# SD_USB_FMU3_REV_G.net
KiCad netlist of a schematic drawn in Altium Designer
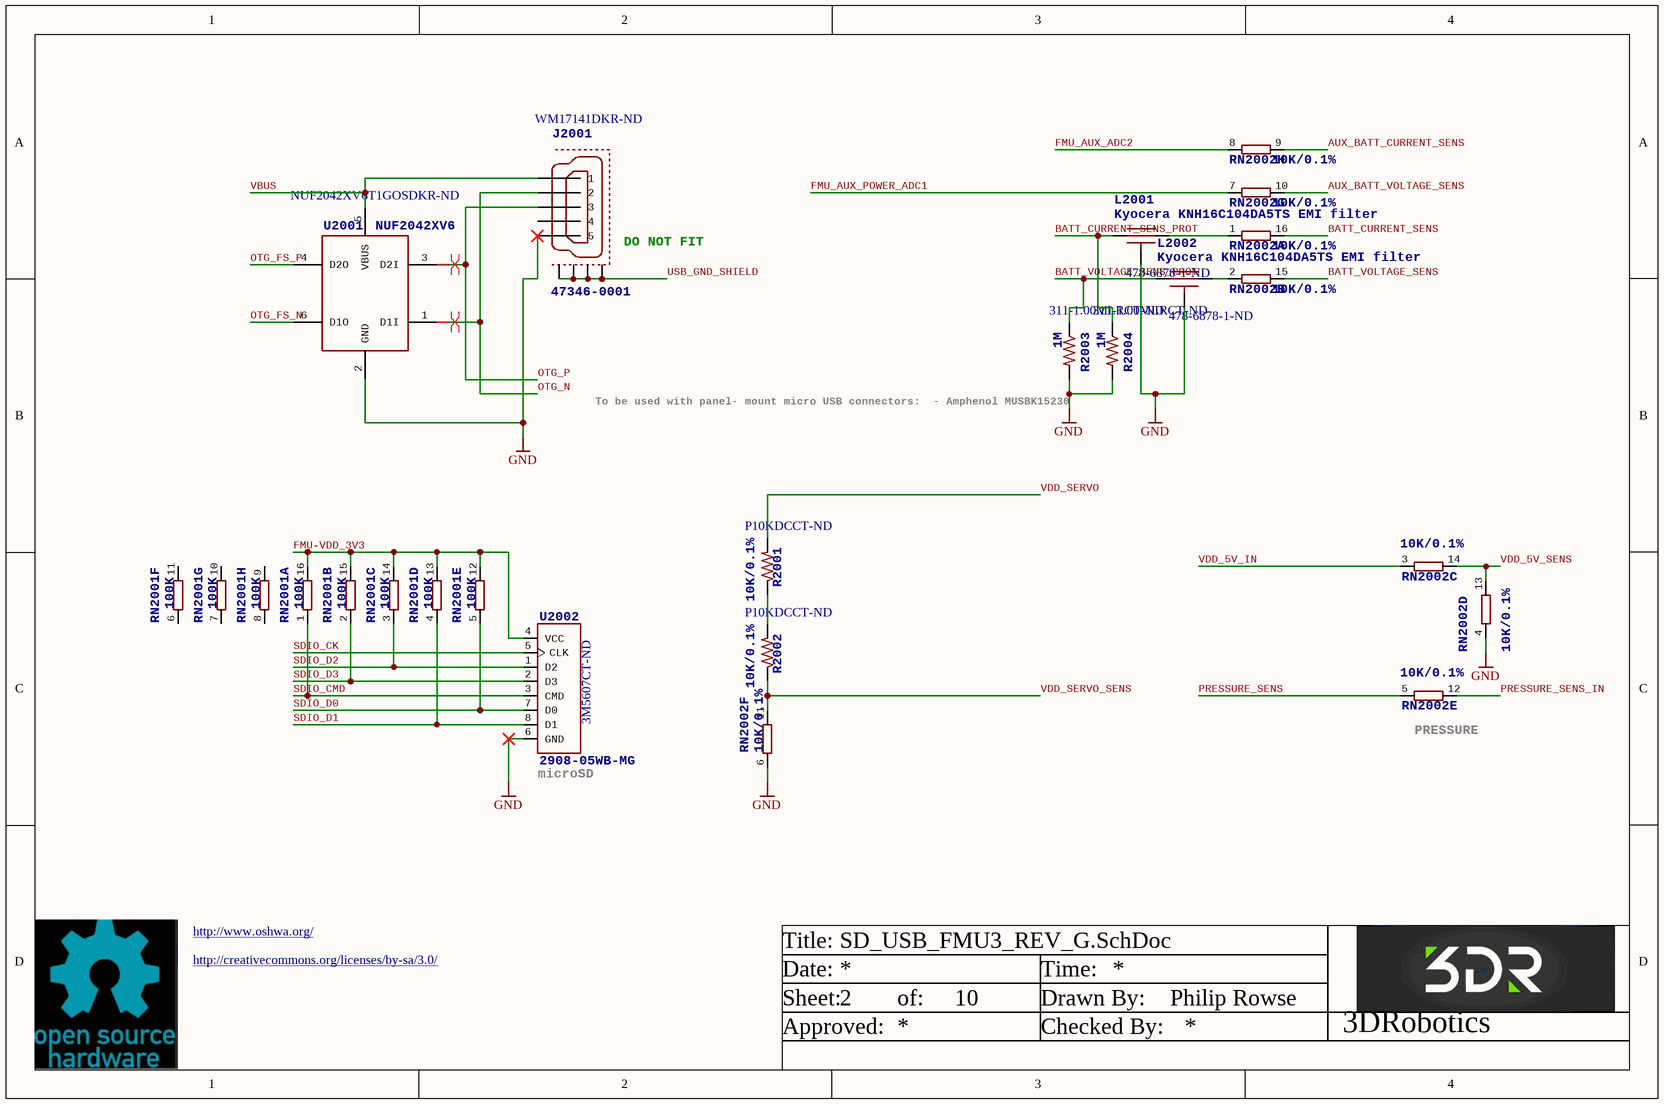
[diagram p0: SD_USB_FMU3_REV_G.SchDoc]

(export (version "E")
  (design (tool "Eeschema 10.0.6"))
  (components
    (comp (ref "J2001")
      (value "47346-0001")
      (footprint "MOLEX-47346-0001")
      (description "MICRO USB B, BOTTOM MOUNT")
      (fields
        (field (name "SUPPLIER PART NUMBER 1") "WM17141DKR-ND")
        (field (name "3DR_PARTNO") "ECM0486")
        (field (name "PARTNO") "0473460001")
      )
      (libsource (lib "pixhawk2") (part "MOLEX-47346-0001"))
    )
    (comp (ref "L2001")
      (value "Kyocera KNH16C104DA5TS EMI filter")
      (footprint "KYOCERA-KNH16-DA")
      (description "FILTER CAP 0.1UF 2A 25V 0603")
      (fields
        (field (name "SUPPLIER PART NUMBER 1") "478-6878-1-ND")
        (field (name "3DR_PARTNO") "ECM0719")
        (field (name "PARTNO") "KNH16C104DA5TS")
      )
      (libsource (lib "pixhawk2") (part "KNH16C104DA5TS"))
    )
    (comp (ref "L2002")
      (value "Kyocera KNH16C104DA5TS EMI filter")
      (footprint "KYOCERA-KNH16-DA")
      (description "FILTER CAP 0.1UF 2A 25V 0603")
      (fields
        (field (name "SUPPLIER PART NUMBER 1") "478-6878-1-ND")
        (field (name "3DR_PARTNO") "ECM0719")
        (field (name "PARTNO") "KNH16C104DA5TS")
      )
      (libsource (lib "pixhawk2") (part "KNH16C104DA5TS"))
    )
    (comp (ref "R2001")
      (value "10K/0.1%")
      (footprint "0402-RES")
      (description "RES 10K OHM 1/16W .1% 0402 SMD")
      (fields
        (field (name "SUPPLIER PART NUMBER 1") "P10KDCCT-ND")
        (field (name "3DR_PARTNO") "ECM0810")
        (field (name "PARTNO") "ERA-2AEB103X")
      )
      (libsource (lib "pixhawk2") (part "RESISTOR0402-RES"))
    )
    (comp (ref "R2002")
      (value "10K/0.1%")
      (footprint "0402-RES")
      (description "RES 10K OHM 1/16W .1% 0402 SMD")
      (fields
        (field (name "SUPPLIER PART NUMBER 1") "P10KDCCT-ND")
        (field (name "3DR_PARTNO") "ECM0810")
        (field (name "PARTNO") "ERA-2AEB103X")
      )
      (libsource (lib "pixhawk2") (part "RESISTOR0402-RES"))
    )
    (comp (ref "R2003")
      (value "1M")
      (footprint "0402-RES")
      (description "RES 1M OHM 1/16W 1% 0402 SMD")
      (fields
        (field (name "PARTNO") "RC0402FR-071ML")
        (field (name "SUPPLIER PART NUMBER 1") "311-1.00MLRCT-ND")
        (field (name "3DR_PARTNO") "ECM0806")
      )
      (libsource (lib "pixhawk2") (part "RESISTOR0402-RES"))
    )
    (comp (ref "R2004")
      (value "1M")
      (footprint "0402-RES")
      (description "RES 1M OHM 1/16W 1% 0402 SMD")
      (fields
        (field (name "PARTNO") "RC0402FR-071ML")
        (field (name "SUPPLIER PART NUMBER 1") "311-1.00MLRCT-ND")
        (field (name "3DR_PARTNO") "ECM0806")
      )
      (libsource (lib "pixhawk2") (part "RESISTOR0402-RES"))
    )
    (comp (ref "RN2001")
      (value "100K")
      (footprint "EXB2HV")
      (description "RES ARRAY 100K OHM 8 RES 1506")
      (fields (field (name "PARTNO") "EXB-2HV104JV") (field (name "3DR_PARTNO") "ECM0101"))
      (libsource (lib "pixhawk2") (part "8R-NEXB2HV-100K"))
    )
    (comp (ref "RN2002")
      (value "10K/0.1%")
      (footprint "EXB2HV")
      (description "RES ARRAY 10K OHM 8 RES 1506")
      (fields (field (name "PARTNO") "EXB-2HV103JV") (field (name "3DR_PARTNO") "ECM0546"))
      (libsource (lib "pixhawk2") (part "8R-NEXB2HV-10K"))
    )
    (comp (ref "U2001")
      (value "NUF2042XV6")
      (footprint "SOT563-6")
      (description "IC FILTER USB ESD PROTECT SOT363")
      (fields
        (field (name "PARTNO") "NUF2042XV6T1G")
        (field (name "SUPPLIER PART NUMBER 1") "NUF2042XV6T1GOSDKR-ND")
        (field (name "3DR_PARTNO") "ECM0836")
      )
      (libsource (lib "pixhawk2") (part "NUF2042XV6"))
    )
    (comp (ref "U2002")
      (value "2908-05WB-MG")
      (footprint "MICROSD")
      (description "CONN MICRO SD CARD PUSH-PUSH R/A")
      (fields (field (name "SUPPLIER PART NUMBER 1") "3M5607CT-ND") (field (name "3DR_PARTNO") "ECM0485"))
      (libsource (lib "baseboard") (part "MICROSDSDI"))
    )
  )
  (nets
    (net (code "1") (name "/AUX_BATT_CURRENT_SENS") (class "Default")
      (node (ref "RN2002") (pin "9") (pinfunction "2_9") (pintype "passive"))
    )
    (net (code "2") (name "/AUX_BATT_VOLTAGE_SENS") (class "Default")
      (node (ref "RN2002") (pin "10") (pinfunction "2_10") (pintype "passive"))
    )
    (net (code "3") (name "/BATT_CURRENT_SENS") (class "Default")
      (node (ref "RN2002") (pin "16") (pinfunction "2_16") (pintype "passive"))
    )
    (net (code "4") (name "/BATT_CURRENT_SENS_PROT") (class "Default")
      (node (ref "L2001") (pin "P$1") (pinfunction "P$1_P$1") (pintype "passive"))
      (node (ref "R2004") (pin "P$1") (pinfunction "1_P$1") (pintype "passive"))
    )
    (net (code "5") (name "/BATT_VOLTAGE_SENS") (class "Default")
      (node (ref "RN2002") (pin "15") (pinfunction "2_15") (pintype "passive"))
    )
    (net (code "6") (name "/BATT_VOLTAGE_SENS_PROT") (class "Default")
      (node (ref "L2002") (pin "P$1") (pinfunction "P$1_P$1") (pintype "passive"))
      (node (ref "R2003") (pin "P$1") (pinfunction "1_P$1") (pintype "passive"))
    )
    (net (code "7") (name "/FMU-VDD_3V3") (class "Default")
      (node (ref "RN2001") (pin "12") (pinfunction "2_12") (pintype "passive"))
      (node (ref "RN2001") (pin "13") (pinfunction "2_13") (pintype "passive"))
      (node (ref "RN2001") (pin "14") (pinfunction "2_14") (pintype "passive"))
      (node (ref "RN2001") (pin "15") (pinfunction "2_15") (pintype "passive"))
      (node (ref "RN2001") (pin "16") (pinfunction "2_16") (pintype "passive"))
      (node (ref "U2002") (pin "4") (pinfunction "VCC_4") (pintype "passive"))
    )
    (net (code "8") (name "/FMU_AUX_ADC2") (class "Default")
      (node (ref "RN2002") (pin "8") (pinfunction "1_8") (pintype "passive"))
    )
    (net (code "9") (name "/FMU_AUX_POWER_ADC1") (class "Default")
      (node (ref "RN2002") (pin "7") (pinfunction "1_7") (pintype "passive"))
    )
    (net (code "10") (name "/OTG_FS_N") (class "Default")
      (node (ref "U2001") (pin "6") (pinfunction "D1O_6") (pintype "passive"))
    )
    (net (code "11") (name "/OTG_FS_P") (class "Default")
      (node (ref "U2001") (pin "4") (pinfunction "D2O_4") (pintype "passive"))
    )
    (net (code "12") (name "/OTG_N") (class "Default")
      (node (ref "J2001") (pin "D-") (pinfunction "2_D-") (pintype "passive"))
      (node (ref "U2001") (pin "1") (pinfunction "D1I_1") (pintype "passive"))
    )
    (net (code "13") (name "/OTG_P") (class "Default")
      (node (ref "J2001") (pin "D+") (pinfunction "3_D+") (pintype "passive"))
      (node (ref "U2001") (pin "3") (pinfunction "D2I_3") (pintype "passive"))
    )
    (net (code "14") (name "/PRESSURE_SENS") (class "Default")
      (node (ref "RN2002") (pin "5") (pinfunction "1_5") (pintype "passive"))
    )
    (net (code "15") (name "/PRESSURE_SENS_IN") (class "Default")
      (node (ref "RN2002") (pin "12") (pinfunction "2_12") (pintype "passive"))
    )
    (net (code "16") (name "/SDIO_CK") (class "Default")
      (node (ref "U2002") (pin "5") (pinfunction "CLK_5") (pintype "passive"))
    )
    (net (code "17") (name "/SDIO_CMD") (class "Default")
      (node (ref "RN2001") (pin "1") (pinfunction "1_1") (pintype "passive"))
      (node (ref "U2002") (pin "3") (pinfunction "CMD_3") (pintype "passive"))
    )
    (net (code "18") (name "/SDIO_D0") (class "Default")
      (node (ref "RN2001") (pin "5") (pinfunction "1_5") (pintype "passive"))
      (node (ref "U2002") (pin "7") (pinfunction "D0_7") (pintype "passive"))
    )
    (net (code "19") (name "/SDIO_D1") (class "Default")
      (node (ref "RN2001") (pin "4") (pinfunction "1_4") (pintype "passive"))
      (node (ref "U2002") (pin "8") (pinfunction "D1_8") (pintype "passive"))
    )
    (net (code "20") (name "/SDIO_D2") (class "Default")
      (node (ref "RN2001") (pin "3") (pinfunction "1_3") (pintype "passive"))
      (node (ref "U2002") (pin "1") (pinfunction "D2_1") (pintype "passive"))
    )
    (net (code "21") (name "/SDIO_D3") (class "Default")
      (node (ref "RN2001") (pin "2") (pinfunction "1_2") (pintype "passive"))
      (node (ref "U2002") (pin "2") (pinfunction "D3_2") (pintype "passive"))
    )
    (net (code "22") (name "/USB_GND_SHIELD") (class "Default")
      (node (ref "J2001") (pin "GND1") (pinfunction "GND1_GND1") (pintype "passive"))
      (node (ref "J2001") (pin "GND2") (pinfunction "GND2_GND2") (pintype "passive"))
      (node (ref "J2001") (pin "GND3") (pinfunction "GND3_GND3") (pintype "passive"))
      (node (ref "J2001") (pin "GND4") (pinfunction "GND4_GND4") (pintype "passive"))
    )
    (net (code "23") (name "/VBUS") (class "Default")
      (node (ref "J2001") (pin "VBUS") (pinfunction "1_VBUS") (pintype "open_emitter"))
      (node (ref "U2001") (pin "5") (pinfunction "VBUS_5") (pintype "passive"))
    )
    (net (code "24") (name "/VDD_5V_IN") (class "Default")
      (node (ref "RN2002") (pin "3") (pinfunction "1_3") (pintype "passive"))
    )
    (net (code "25") (name "/VDD_5V_SENS") (class "Default")
      (node (ref "RN2002") (pin "13") (pinfunction "2_13") (pintype "passive"))
      (node (ref "RN2002") (pin "14") (pinfunction "2_14") (pintype "passive"))
    )
    (net (code "26") (name "/VDD_SERVO") (class "Default")
      (node (ref "R2001") (pin "P$2") (pinfunction "2_P$2") (pintype "passive"))
    )
    (net (code "27") (name "/VDD_SERVO_SENS") (class "Default")
      (node (ref "R2002") (pin "P$1") (pinfunction "1_P$1") (pintype "passive"))
      (node (ref "RN2002") (pin "11") (pinfunction "2_11") (pintype "passive"))
    )
    (net (code "28") (name "GND") (class "Default")
      (node (ref "J2001") (pin "GND") (pinfunction "5_GND") (pintype "open_emitter"))
      (node (ref "L2001") (pin "GND") (pinfunction "GND_GND") (pintype "passive"))
      (node (ref "L2002") (pin "GND") (pinfunction "GND_GND") (pintype "passive"))
      (node (ref "R2003") (pin "P$2") (pinfunction "2_P$2") (pintype "passive"))
      (node (ref "R2004") (pin "P$2") (pinfunction "2_P$2") (pintype "passive"))
      (node (ref "RN2002") (pin "4") (pinfunction "1_4") (pintype "passive"))
      (node (ref "RN2002") (pin "6") (pinfunction "1_6") (pintype "passive"))
      (node (ref "U2001") (pin "2") (pinfunction "GND_2") (pintype "passive"))
      (node (ref "U2002") (pin "6") (pinfunction "GND_6") (pintype "open_emitter"))
    )
    (net (code "29") (name "Net-(L2001-PadP$2)") (class "Default")
      (node (ref "L2001") (pin "P$2") (pinfunction "P$2_P$2") (pintype "passive"))
      (node (ref "RN2002") (pin "1") (pinfunction "1_1") (pintype "passive"))
    )
    (net (code "30") (name "Net-(R2001-1)") (class "Default")
      (node (ref "R2001") (pin "P$1") (pinfunction "1_P$1") (pintype "passive"))
      (node (ref "R2002") (pin "P$2") (pinfunction "2_P$2") (pintype "passive"))
    )
    (net (code "31") (name "Net-(RN2002B-1)") (class "Default")
      (node (ref "L2002") (pin "P$2") (pinfunction "P$2_P$2") (pintype "passive"))
      (node (ref "RN2002") (pin "2") (pinfunction "1_2") (pintype "passive"))
    )
    (net (code "32") (name "unconnected-(J2001-4-PadID)") (class "Default")
      (node (ref "J2001") (pin "ID") (pinfunction "4_ID") (pintype "passive"))
    )
    (net (code "33") (name "unconnected-(RN2001F-1-Pad6)") (class "Default")
      (node (ref "RN2001") (pin "6") (pinfunction "1_6") (pintype "passive"))
    )
    (net (code "34") (name "unconnected-(RN2001F-2-Pad11)") (class "Default")
      (node (ref "RN2001") (pin "11") (pinfunction "2_11") (pintype "passive"))
    )
    (net (code "35") (name "unconnected-(RN2001G-1-Pad7)") (class "Default")
      (node (ref "RN2001") (pin "7") (pinfunction "1_7") (pintype "passive"))
    )
    (net (code "36") (name "unconnected-(RN2001G-2-Pad10)") (class "Default")
      (node (ref "RN2001") (pin "10") (pinfunction "2_10") (pintype "passive"))
    )
    (net (code "37") (name "unconnected-(RN2001H-1-Pad8)") (class "Default")
      (node (ref "RN2001") (pin "8") (pinfunction "1_8") (pintype "passive"))
    )
    (net (code "38") (name "unconnected-(RN2001H-2-Pad9)") (class "Default")
      (node (ref "RN2001") (pin "9") (pinfunction "2_9") (pintype "passive"))
    )
  )
)
